# Adafruit_I2C_FRAM.net
KiCad netlist of a schematic drawn in EAGLE
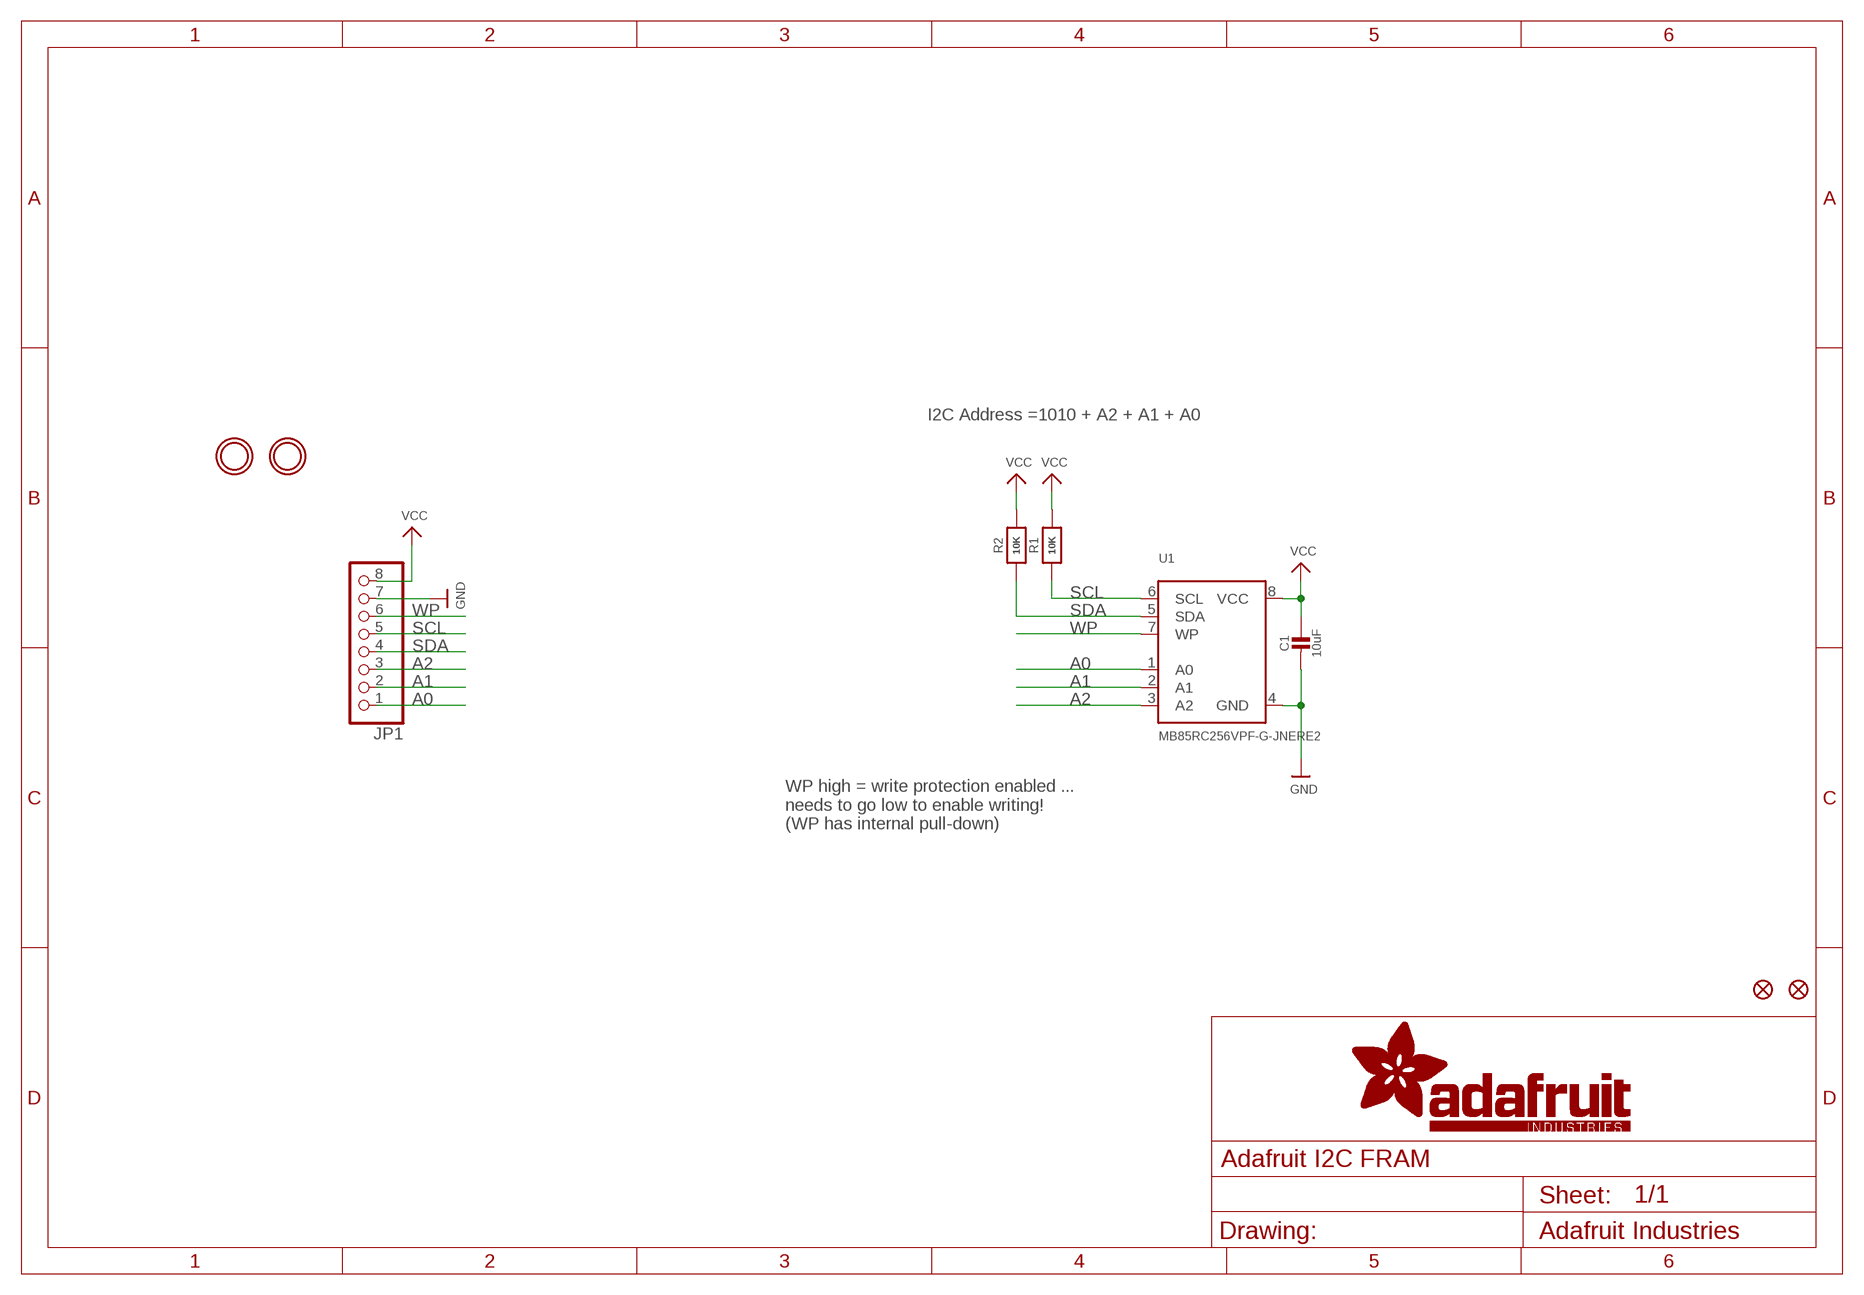
[diagram p0: schematic, sheet 1]

(export (version "E")
  (design (tool "Eeschema 10.0.6"))
  (components
    (comp (ref "C1")
      (value "10uF")
      (footprint "eagle-import:_0805MP")
      (libsource (lib "eagle-import") (part "CAP_CERAMIC_0805MP"))
    )
    (comp (ref "FID1")
      (value "FIDUCIAL\"\"")
      (footprint "eagle-import:FIDUCIAL_1MM")
      (libsource (lib "eagle-import") (part "FIDUCIAL{dblquote}{dblquote}"))
    )
    (comp (ref "FID2")
      (value "FIDUCIAL\"\"")
      (footprint "eagle-import:FIDUCIAL_1MM")
      (libsource (lib "eagle-import") (part "FIDUCIAL{dblquote}{dblquote}"))
    )
    (comp (ref "JP1")
      (value "HEADER-1X870MIL")
      (footprint "eagle-import:1X08_ROUND_70")
      (libsource (lib "eagle-import") (part "HEADER-1X870MIL"))
    )
    (comp (ref "R1")
      (value "10K")
      (footprint "eagle-import:_0805MP")
      (libsource (lib "eagle-import") (part "RESISTOR_0805MP"))
    )
    (comp (ref "R2")
      (value "10K")
      (footprint "eagle-import:_0805MP")
      (libsource (lib "eagle-import") (part "RESISTOR_0805MP"))
    )
    (comp (ref "U$5")
      (value "MOUNTINGHOLE2.5")
      (footprint "eagle-import:MOUNTINGHOLE_2.5_PLATED")
      (libsource (lib "eagle-import") (part "MOUNTINGHOLE2.5"))
    )
    (comp (ref "U$6")
      (value "MOUNTINGHOLE2.5")
      (footprint "eagle-import:MOUNTINGHOLE_2.5_PLATED")
      (libsource (lib "eagle-import") (part "MOUNTINGHOLE2.5"))
    )
    (comp (ref "U1")
      (value "MB85RC256VPF-G-JNERE2")
      (footprint "eagle-import:SOIC8_208MIL")
      (libsource (lib "eagle-import") (part "FRAM_SOIC8_I2C"))
    )
  )
  (nets
    (net (code "1") (name "/A0") (class "Default")
      (node (ref "JP1") (pin "1") (pinfunction "1_1") (pintype "passive"))
      (node (ref "U1") (pin "1") (pinfunction "A0_1") (pintype "input"))
    )
    (net (code "2") (name "/A1") (class "Default")
      (node (ref "JP1") (pin "2") (pinfunction "2_2") (pintype "passive"))
      (node (ref "U1") (pin "2") (pinfunction "A1_2") (pintype "input"))
    )
    (net (code "3") (name "/A2") (class "Default")
      (node (ref "JP1") (pin "3") (pinfunction "3_3") (pintype "passive"))
      (node (ref "U1") (pin "3") (pinfunction "A2_3") (pintype "input"))
    )
    (net (code "4") (name "/SCL") (class "Default")
      (node (ref "JP1") (pin "5") (pinfunction "5_5") (pintype "passive"))
      (node (ref "R1") (pin "1") (pinfunction "1_1") (pintype "passive"))
      (node (ref "U1") (pin "6") (pinfunction "SCL_6") (pintype "input"))
    )
    (net (code "5") (name "/SDA") (class "Default")
      (node (ref "JP1") (pin "4") (pinfunction "4_4") (pintype "passive"))
      (node (ref "R2") (pin "1") (pinfunction "1_1") (pintype "passive"))
      (node (ref "U1") (pin "5") (pinfunction "SDA_5") (pintype "bidirectional"))
    )
    (net (code "6") (name "/WP") (class "Default")
      (node (ref "JP1") (pin "6") (pinfunction "6_6") (pintype "passive"))
      (node (ref "U1") (pin "7") (pinfunction "WP_7") (pintype "input"))
    )
    (net (code "7") (name "GND") (class "Default")
      (node (ref "C1") (pin "2") (pinfunction "2_2") (pintype "passive"))
      (node (ref "JP1") (pin "7") (pinfunction "7_7") (pintype "passive"))
      (node (ref "U1") (pin "4") (pinfunction "GND_4") (pintype "power_in"))
    )
    (net (code "8") (name "VCC") (class "Default")
      (node (ref "C1") (pin "1") (pinfunction "1_1") (pintype "passive"))
      (node (ref "JP1") (pin "8") (pinfunction "8_8") (pintype "passive"))
      (node (ref "R1") (pin "2") (pinfunction "2_2") (pintype "passive"))
      (node (ref "R2") (pin "2") (pinfunction "2_2") (pintype "passive"))
      (node (ref "U1") (pin "8") (pinfunction "VCC_8") (pintype "power_in"))
    )
  )
)
